# Conn_pcb5.net
KiCad netlist of a schematic drawn in EAGLE
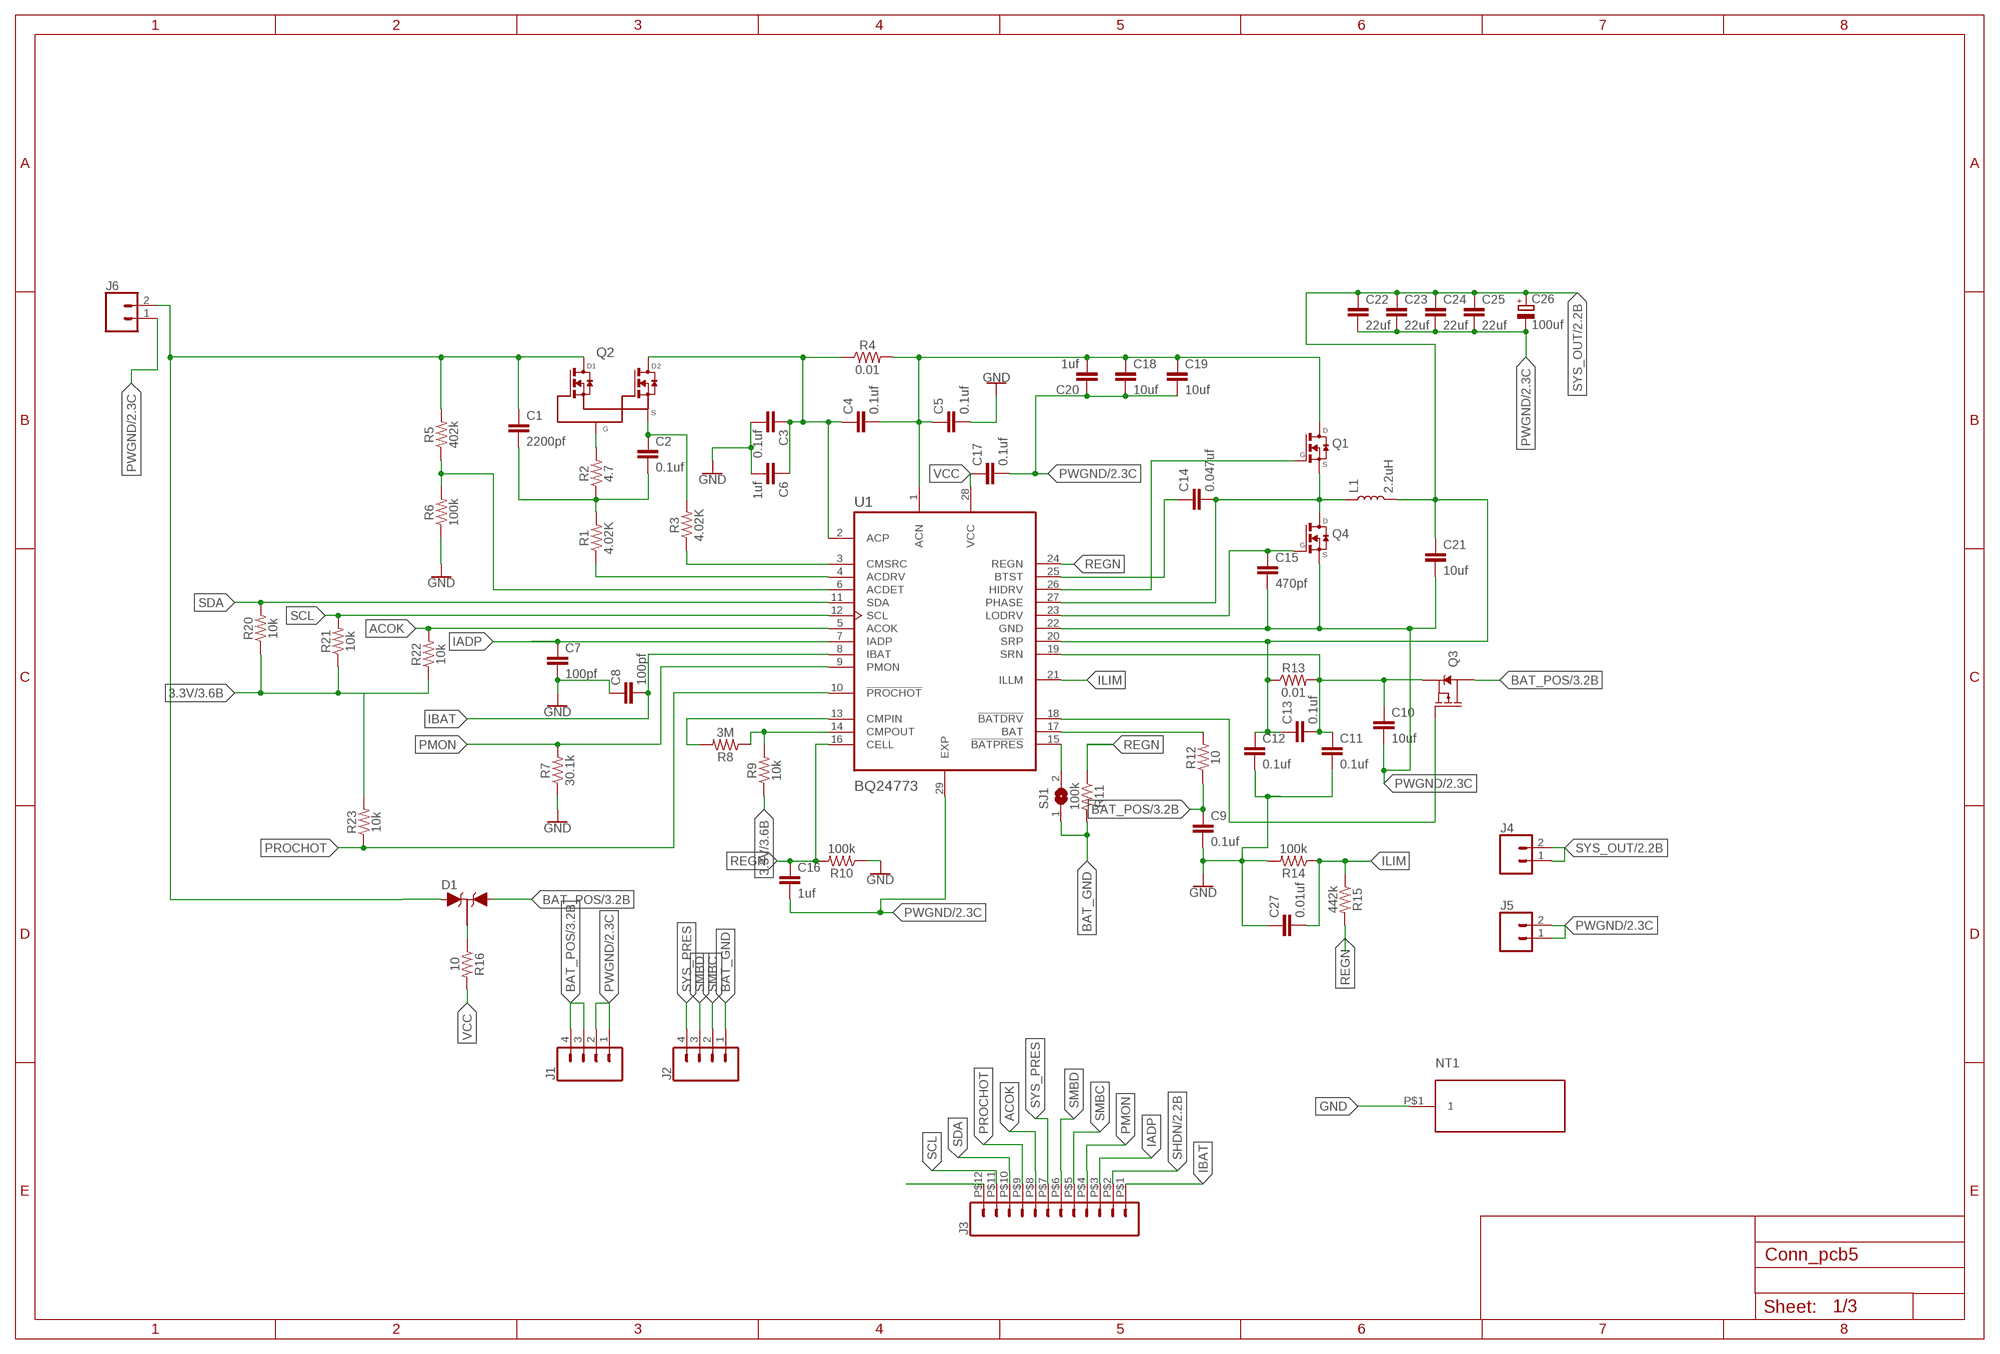
[diagram p0: schematic, sheet 1]
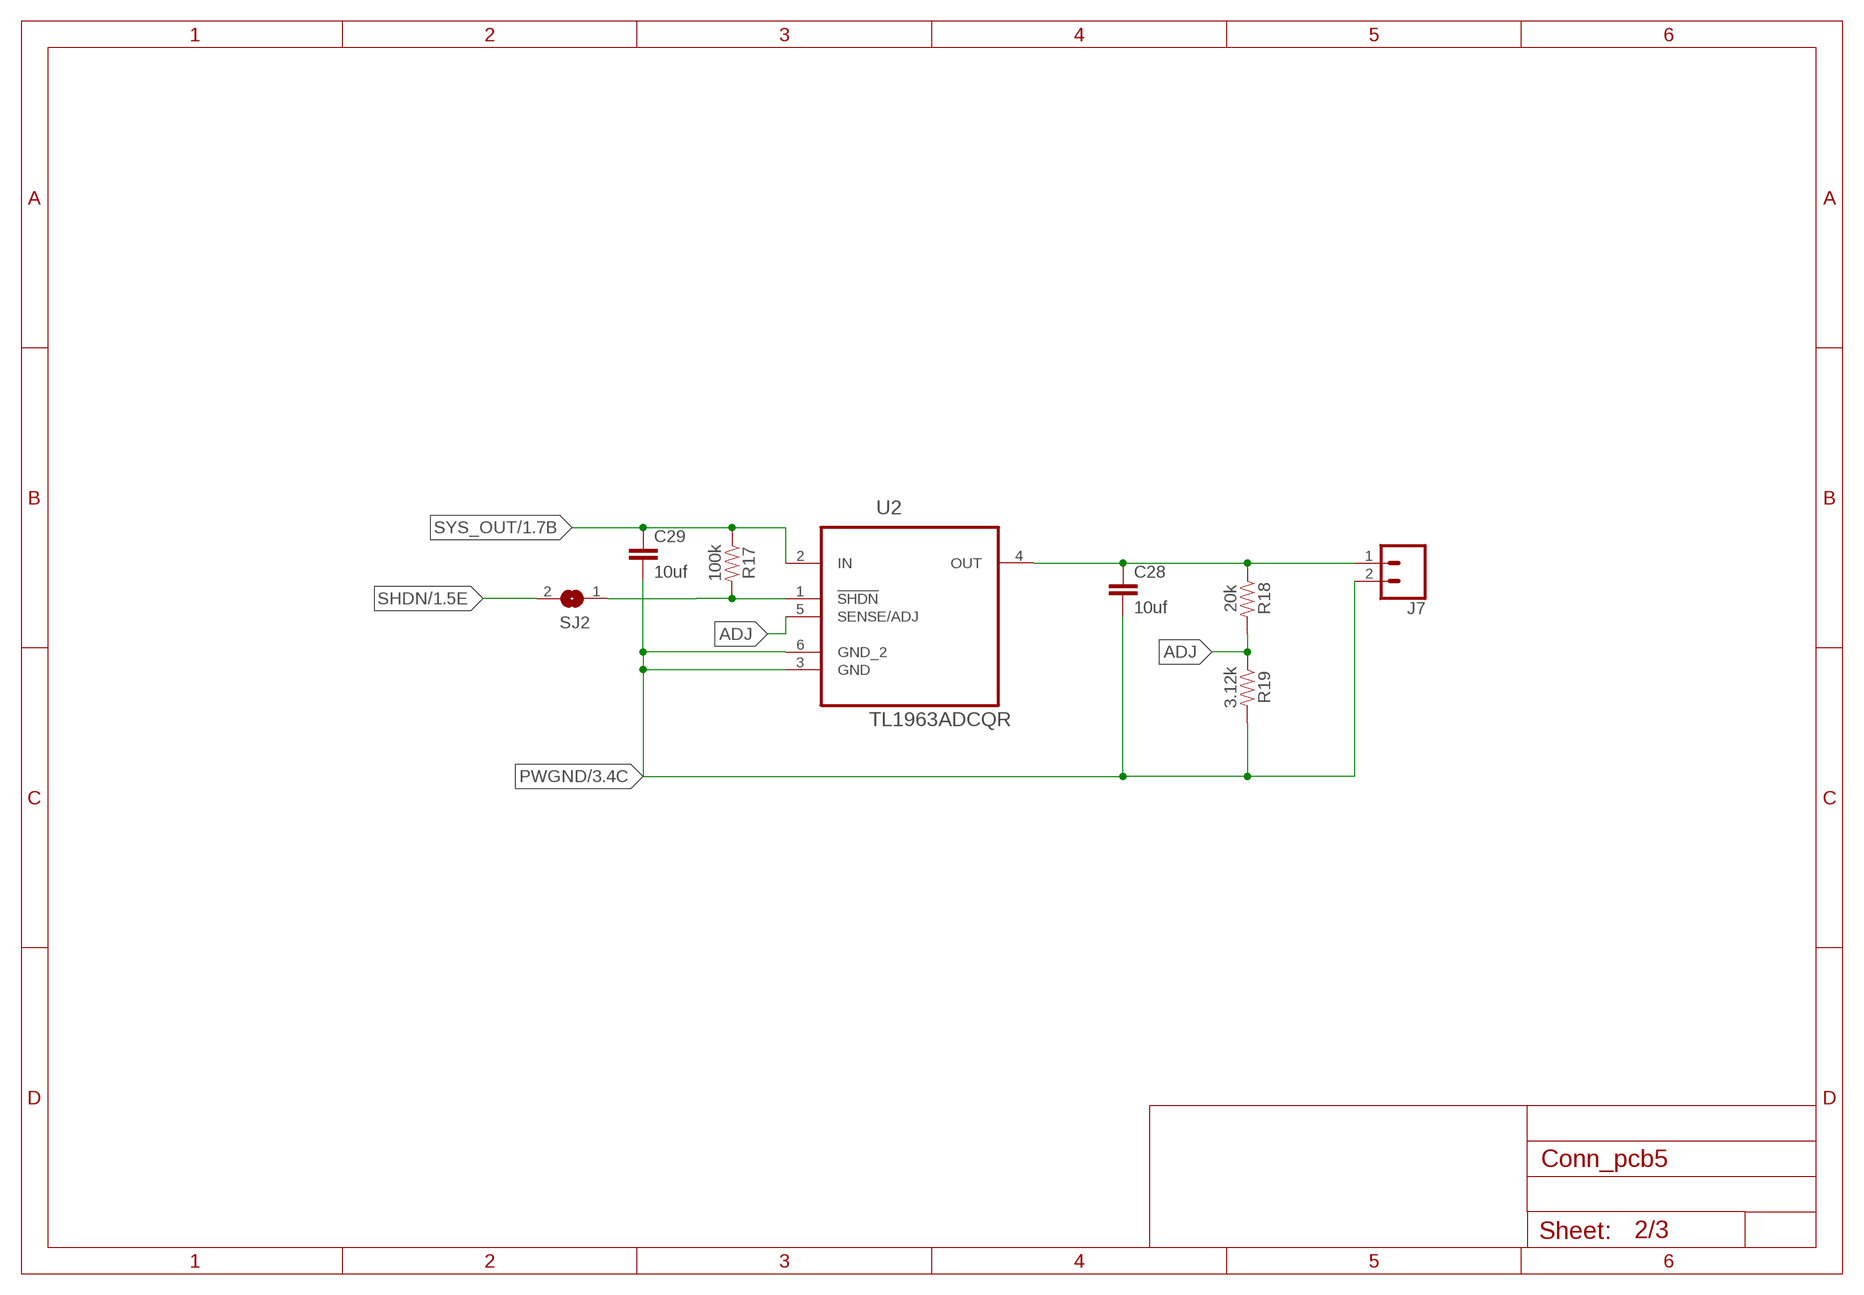
[diagram p1: schematic, sheet 2]
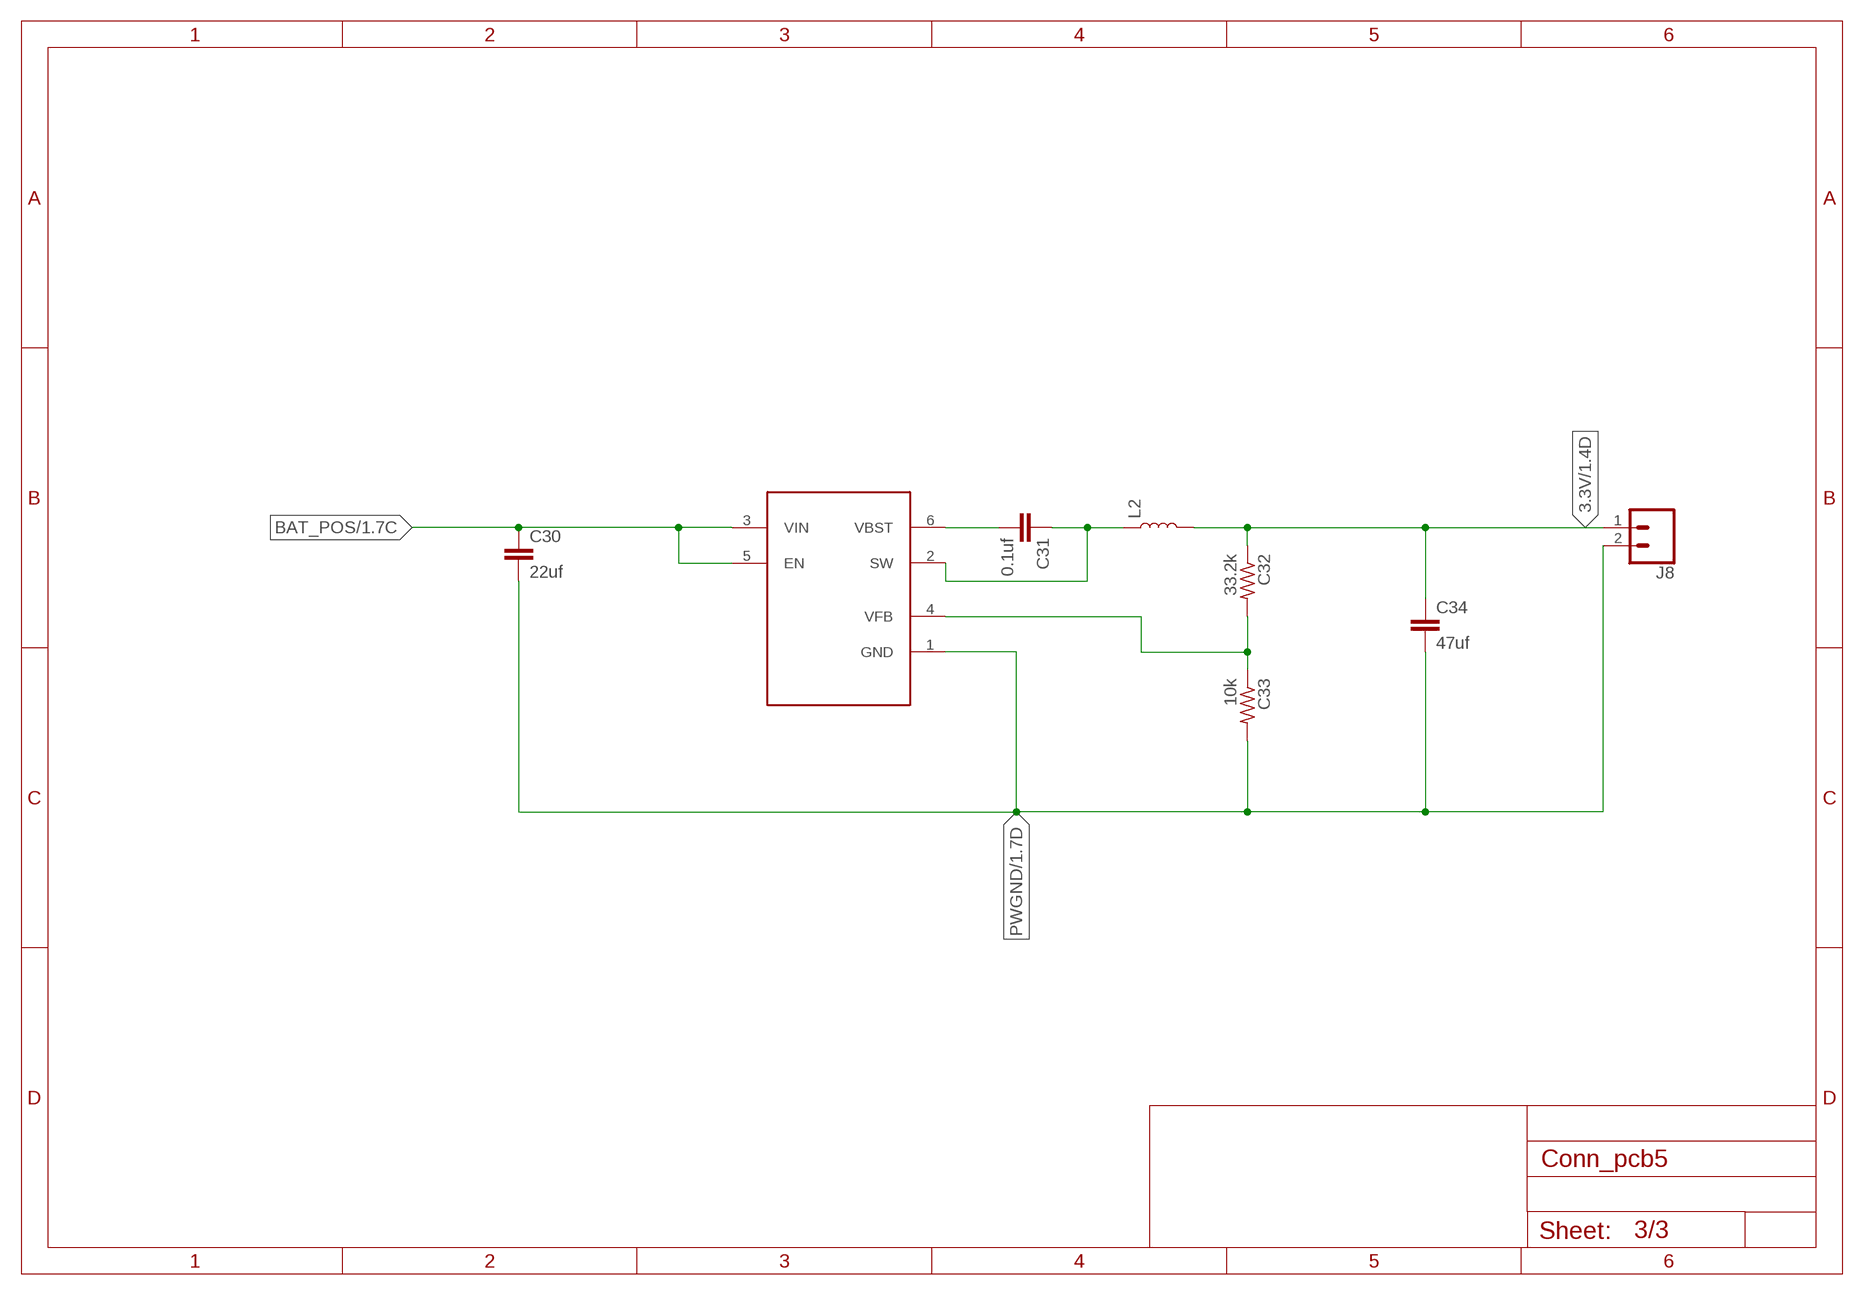
[diagram p2: schematic, sheet 3]

(export (version "E")
  (design (tool "Eeschema 10.0.6"))
  (components
    (comp (ref "C28")
      (value "10uf")
      (footprint "eagle-import:C0805K")
      (libsource (lib "eagle-import") (part "C-EUC0805K"))
    )
    (comp (ref "C29")
      (value "10uf")
      (footprint "eagle-import:C0805K")
      (libsource (lib "eagle-import") (part "C-EUC0805K"))
    )
    (comp (ref "J7")
      (value "CONN_02")
      (footprint "eagle-import:1X02")
      (libsource (lib "eagle-import") (part "CONN_02"))
    )
    (comp (ref "R17")
      (value "100k")
      (footprint "eagle-import:0402")
      (libsource (lib "eagle-import") (part "RES4K04020402"))
    )
    (comp (ref "R18")
      (value "20k")
      (footprint "eagle-import:0402")
      (libsource (lib "eagle-import") (part "RES4K04020402"))
    )
    (comp (ref "R19")
      (value "3.12k")
      (footprint "eagle-import:0402")
      (libsource (lib "eagle-import") (part "RES4K04020402"))
    )
    (comp (ref "SJ2") (value "SJ") (footprint "eagle-import:SJ") (libsource (lib "eagle-import") (part "SJ")))
    (comp (ref "U2")
      (value "TL1963ADCQR")
      (footprint "eagle-import:SOT127P706X180-6")
      (libsource (lib "eagle-import") (part "TL1963ADCQR"))
    )
    (comp (ref "C30")
      (value "22uf")
      (footprint "eagle-import:C1206")
      (libsource (lib "eagle-import") (part "C-EUC1206"))
    )
    (comp (ref "C31")
      (value "0.1uf")
      (footprint "eagle-import:CAPC1005X50")
      (libsource (lib "eagle-import") (part "CAP0402"))
    )
    (comp (ref "C32")
      (value "33.2k")
      (footprint "eagle-import:R0805")
      (libsource (lib "eagle-import") (part "R-US_R0805"))
    )
    (comp (ref "C33")
      (value "10k")
      (footprint "eagle-import:R0603")
      (libsource (lib "eagle-import") (part "R-US_R0603"))
    )
    (comp (ref "C34")
      (value "47uf")
      (footprint "eagle-import:C1206K")
      (libsource (lib "eagle-import") (part "C-EUC1206K"))
    )
    (comp (ref "J8")
      (value "CONN_02")
      (footprint "eagle-import:1X02")
      (libsource (lib "eagle-import") (part "CONN_02"))
    )
    (comp (ref "L2")
      (value "ASPI-4030S-3R3M-T")
      (footprint "eagle-import:INDDFN400X400X300-2")
      (libsource (lib "eagle-import") (part "ASPI-4030S-3R3M-T"))
    )
    (comp (ref "U3")
      (value "TPS561208DDCR")
      (footprint "eagle-import:SOT95P280X110-6")
      (libsource (lib "eagle-import") (part "TPS561208DDCR"))
    )
    (comp (ref "C1")
      (value "2200pf")
      (footprint "eagle-import:CAPC1005X50")
      (libsource (lib "eagle-import") (part "CAP0402"))
    )
    (comp (ref "C2")
      (value "0.1uf")
      (footprint "eagle-import:CAPC1005X50")
      (libsource (lib "eagle-import") (part "CAP0402"))
    )
    (comp (ref "C3")
      (value "0.1uf")
      (footprint "eagle-import:CAPC1005X50")
      (libsource (lib "eagle-import") (part "CAP0402"))
    )
    (comp (ref "C4")
      (value "0.1uf")
      (footprint "eagle-import:CAPC1005X50")
      (libsource (lib "eagle-import") (part "CAP0402"))
    )
    (comp (ref "C5")
      (value "0.1uf")
      (footprint "eagle-import:CAPC1005X50")
      (libsource (lib "eagle-import") (part "CAP0402"))
    )
    (comp (ref "C6")
      (value "1uf")
      (footprint "eagle-import:CAPC1005X50")
      (libsource (lib "eagle-import") (part "CAP0402"))
    )
    (comp (ref "C7")
      (value "100pf")
      (footprint "eagle-import:CAPC1005X50")
      (libsource (lib "eagle-import") (part "CAP0402"))
    )
    (comp (ref "C8")
      (value "100pf")
      (footprint "eagle-import:CAPC1005X50")
      (libsource (lib "eagle-import") (part "CAP0402"))
    )
    (comp (ref "C9")
      (value "0.1uf")
      (footprint "eagle-import:CAPC1005X50")
      (libsource (lib "eagle-import") (part "CAP0402"))
    )
    (comp (ref "C10")
      (value "10uf")
      (footprint "eagle-import:C0805K")
      (libsource (lib "eagle-import") (part "C-EUC0805K"))
    )
    (comp (ref "C11")
      (value "0.1uf")
      (footprint "eagle-import:CAPC1005X50")
      (libsource (lib "eagle-import") (part "CAP0402"))
    )
    (comp (ref "C12")
      (value "0.1uf")
      (footprint "eagle-import:CAPC1005X50")
      (libsource (lib "eagle-import") (part "CAP0402"))
    )
    (comp (ref "C13")
      (value "0.1uf")
      (footprint "eagle-import:CAPC1005X50")
      (libsource (lib "eagle-import") (part "CAP0402"))
    )
    (comp (ref "C14")
      (value "0.047uf")
      (footprint "eagle-import:CAPC1005X50")
      (libsource (lib "eagle-import") (part "CAP0402"))
    )
    (comp (ref "C15")
      (value "470pf")
      (footprint "eagle-import:CAPC1005X50")
      (libsource (lib "eagle-import") (part "CAP0402"))
    )
    (comp (ref "C16")
      (value "1uf")
      (footprint "eagle-import:CAPC1005X50")
      (libsource (lib "eagle-import") (part "CAP0402"))
    )
    (comp (ref "C17")
      (value "0.1uf")
      (footprint "eagle-import:CAPC1005X50")
      (libsource (lib "eagle-import") (part "CAP0402"))
    )
    (comp (ref "C18")
      (value "10uf")
      (footprint "eagle-import:C0805K")
      (libsource (lib "eagle-import") (part "C-EUC0805K"))
    )
    (comp (ref "C19")
      (value "10uf")
      (footprint "eagle-import:C0805K")
      (libsource (lib "eagle-import") (part "C-EUC0805K"))
    )
    (comp (ref "C20")
      (value "1uf")
      (footprint "eagle-import:CAPC1005X50")
      (libsource (lib "eagle-import") (part "CAP0402"))
    )
    (comp (ref "C21")
      (value "10uf")
      (footprint "eagle-import:C0805K")
      (libsource (lib "eagle-import") (part "C-EUC0805K"))
    )
    (comp (ref "C22")
      (value "22uf")
      (footprint "eagle-import:C1206")
      (libsource (lib "eagle-import") (part "C-EUC1206"))
    )
    (comp (ref "C23")
      (value "22uf")
      (footprint "eagle-import:C1206")
      (libsource (lib "eagle-import") (part "C-EUC1206"))
    )
    (comp (ref "C24")
      (value "22uf")
      (footprint "eagle-import:C1206")
      (libsource (lib "eagle-import") (part "C-EUC1206"))
    )
    (comp (ref "C25")
      (value "22uf")
      (footprint "eagle-import:C1206")
      (libsource (lib "eagle-import") (part "C-EUC1206"))
    )
    (comp (ref "C26")
      (value "100uf")
      (footprint "eagle-import:CAPAE1030X800")
      (libsource (lib "eagle-import") (part "16SVP100M"))
    )
    (comp (ref "C27")
      (value "0.01uf")
      (footprint "eagle-import:CAPC1005X50")
      (libsource (lib "eagle-import") (part "CAP0402"))
    )
    (comp (ref "D1")
      (value "BAT54C-7-F")
      (footprint "eagle-import:SOT95P235X110-3")
      (libsource (lib "eagle-import") (part "BAT54C-7-F"))
    )
    (comp (ref "J1")
      (value "CONN_041.3")
      (footprint "eagle-import:1X04_NO_SILK_1.3")
      (libsource (lib "eagle-import") (part "CONN_041.3"))
    )
    (comp (ref "J2")
      (value "CONN_041.3")
      (footprint "eagle-import:1X04_NO_SILK_1.3")
      (libsource (lib "eagle-import") (part "CONN_041.3"))
    )
    (comp (ref "J3")
      (value "62674-121121ALF")
      (footprint "eagle-import:62674-121121ALF")
      (libsource (lib "eagle-import") (part "62674-121121ALF"))
    )
    (comp (ref "J4")
      (value "CONN_021.4HOLE")
      (footprint "eagle-import:1X02_1.4HOLE")
      (libsource (lib "eagle-import") (part "CONN_021.4HOLE"))
    )
    (comp (ref "J5")
      (value "CONN_021.4HOLE")
      (footprint "eagle-import:1X02_1.4HOLE")
      (libsource (lib "eagle-import") (part "CONN_021.4HOLE"))
    )
    (comp (ref "J6")
      (value "CONN_021.4HOLE")
      (footprint "eagle-import:1X02_1.4HOLE")
      (libsource (lib "eagle-import") (part "CONN_021.4HOLE"))
    )
    (comp (ref "L1")
      (value "2.2uH")
      (footprint "eagle-import:RESM6365X610")
      (libsource (lib "eagle-import") (part "XEL6060-222MEB"))
    )
    (comp (ref "NT1")
      (value "NET_TIE")
      (footprint "eagle-import:NET_TIE")
      (libsource (lib "eagle-import") (part "NET_TIE"))
    )
    (comp (ref "Q1")
      (value "CSD17308Q3")
      (footprint "eagle-import:SON65P330X330X110-8")
      (fields (field (name "SPICEPREFIX") "Q"))
      (libsource (lib "eagle-import") (part "CSD17308Q3"))
    )
    (comp (ref "Q2")
      (value "CSD87312Q3EVSON")
      (footprint "eagle-import:QFN65P330X330X100-12")
      (libsource (lib "eagle-import") (part "CSD87312Q3EVSON"))
    )
    (comp (ref "Q3")
      (value "CSD25402Q3A")
      (footprint "eagle-import:CSD25402Q3A")
      (libsource (lib "eagle-import") (part "CSD25402Q3A"))
    )
    (comp (ref "Q4")
      (value "CSD17308Q3")
      (footprint "eagle-import:SON65P330X330X110-8")
      (fields (field (name "SPICEPREFIX") "Q"))
      (libsource (lib "eagle-import") (part "CSD17308Q3"))
    )
    (comp (ref "R1")
      (value "4.02K")
      (footprint "eagle-import:0402")
      (libsource (lib "eagle-import") (part "RES4K04020402"))
    )
    (comp (ref "R2")
      (value "4.7")
      (footprint "eagle-import:0402")
      (libsource (lib "eagle-import") (part "RES4K04020402"))
    )
    (comp (ref "R3")
      (value "4.02K")
      (footprint "eagle-import:0402")
      (libsource (lib "eagle-import") (part "RES4K04020402"))
    )
    (comp (ref "R4")
      (value "0.01")
      (footprint "eagle-import:1206")
      (libsource (lib "eagle-import") (part "SENSE-RES"))
    )
    (comp (ref "R5")
      (value "402k")
      (footprint "eagle-import:0402")
      (libsource (lib "eagle-import") (part "RES4K04020402"))
    )
    (comp (ref "R6")
      (value "100k")
      (footprint "eagle-import:0402")
      (libsource (lib "eagle-import") (part "RES4K04020402"))
    )
    (comp (ref "R7")
      (value "30.1k")
      (footprint "eagle-import:0402")
      (libsource (lib "eagle-import") (part "RES4K04020402"))
    )
    (comp (ref "R8")
      (value "3M")
      (footprint "eagle-import:0402")
      (libsource (lib "eagle-import") (part "RES4K04020402"))
    )
    (comp (ref "R9")
      (value "10k")
      (footprint "eagle-import:0402")
      (libsource (lib "eagle-import") (part "RES4K04020402"))
    )
    (comp (ref "R10")
      (value "100k")
      (footprint "eagle-import:0402")
      (libsource (lib "eagle-import") (part "RES4K04020402"))
    )
    (comp (ref "R11")
      (value "100k")
      (footprint "eagle-import:0402")
      (libsource (lib "eagle-import") (part "RES4K04020402"))
    )
    (comp (ref "R12")
      (value "10")
      (footprint "eagle-import:0402")
      (libsource (lib "eagle-import") (part "RES4K04020402"))
    )
    (comp (ref "R13")
      (value "0.01")
      (footprint "eagle-import:1206")
      (libsource (lib "eagle-import") (part "SENSE-RES"))
    )
    (comp (ref "R14")
      (value "100k")
      (footprint "eagle-import:0402")
      (libsource (lib "eagle-import") (part "RES4K04020402"))
    )
    (comp (ref "R15")
      (value "442k")
      (footprint "eagle-import:0402")
      (libsource (lib "eagle-import") (part "RES4K04020402"))
    )
    (comp (ref "R16")
      (value "10")
      (footprint "eagle-import:0402")
      (libsource (lib "eagle-import") (part "RES4K04020402"))
    )
    (comp (ref "R20")
      (value "10k")
      (footprint "eagle-import:0402")
      (libsource (lib "eagle-import") (part "RES4K04020402"))
    )
    (comp (ref "R21")
      (value "10k")
      (footprint "eagle-import:0402")
      (libsource (lib "eagle-import") (part "RES4K04020402"))
    )
    (comp (ref "R22")
      (value "10k")
      (footprint "eagle-import:0402")
      (libsource (lib "eagle-import") (part "RES4K04020402"))
    )
    (comp (ref "R23")
      (value "10k")
      (footprint "eagle-import:0402")
      (libsource (lib "eagle-import") (part "RES4K04020402"))
    )
    (comp (ref "SJ1") (value "SJ") (footprint "eagle-import:SJ") (libsource (lib "eagle-import") (part "SJ")))
    (comp (ref "U1")
      (value "BQ24773")
      (footprint "eagle-import:QFN40P400X400X80-29T240")
      (libsource (lib "eagle-import") (part "BQ24773"))
    )
  )
  (nets
    (net (code "1") (name "3.3V") (class "Default")
      (node (ref "C32") (pin "1") (pinfunction "1_1") (pintype "passive"))
      (node (ref "C34") (pin "1") (pinfunction "1_1") (pintype "passive"))
      (node (ref "J8") (pin "1") (pinfunction "1_1") (pintype "passive"))
      (node (ref "L2") (pin "2") (pinfunction "2_2") (pintype "passive"))
      (node (ref "R20") (pin "1") (pinfunction "1_1") (pintype "passive"))
      (node (ref "R21") (pin "1") (pinfunction "1_1") (pintype "passive"))
      (node (ref "R22") (pin "1") (pinfunction "1_1") (pintype "passive"))
      (node (ref "R23") (pin "2") (pinfunction "2_2") (pintype "passive"))
      (node (ref "R9") (pin "1") (pinfunction "1_1") (pintype "passive"))
    )
    (net (code "2") (name "ACOK") (class "Default")
      (node (ref "J3") (pin "P$8") (pinfunction "8_P$8") (pintype "passive"))
      (node (ref "R22") (pin "2") (pinfunction "2_2") (pintype "passive"))
      (node (ref "U1") (pin "5") (pinfunction "ACOK_5") (pintype "output"))
    )
    (net (code "3") (name "ADJ") (class "Default")
      (node (ref "R18") (pin "2") (pinfunction "2_2") (pintype "passive"))
      (node (ref "R19") (pin "1") (pinfunction "1_1") (pintype "passive"))
      (node (ref "U2") (pin "5") (pinfunction "SENSE/ADJ_5") (pintype "input"))
    )
    (net (code "4") (name "BAT_GND") (class "Default")
      (node (ref "J2") (pin "1") (pinfunction "1_1") (pintype "passive"))
      (node (ref "R11") (pin "2") (pinfunction "2_2") (pintype "passive"))
      (node (ref "SJ1") (pin "1") (pinfunction "1_1") (pintype "passive"))
    )
    (net (code "5") (name "BAT_POS") (class "Default")
      (node (ref "C30") (pin "1") (pinfunction "1_1") (pintype "passive"))
      (node (ref "C9") (pin "1") (pinfunction "1_1") (pintype "passive"))
      (node (ref "D1") (pin "2") (pinfunction "A2_2") (pintype "passive"))
      (node (ref "J1") (pin "3") (pinfunction "3_3") (pintype "passive"))
      (node (ref "J1") (pin "4") (pinfunction "4_4") (pintype "passive"))
      (node (ref "Q3") (pin "1") (pinfunction "D_1") (pintype "bidirectional"))
      (node (ref "Q3") (pin "2") (pinfunction "D_2") (pintype "bidirectional"))
      (node (ref "Q3") (pin "3") (pinfunction "D_3") (pintype "bidirectional"))
      (node (ref "R12") (pin "1") (pinfunction "1_1") (pintype "passive"))
      (node (ref "U3") (pin "3") (pinfunction "VIN_3") (pintype "bidirectional"))
      (node (ref "U3") (pin "5") (pinfunction "EN_5") (pintype "bidirectional"))
    )
    (net (code "6") (name "GND") (class "Default")
      (node (ref "C11") (pin "2") (pinfunction "2_2") (pintype "passive"))
      (node (ref "C12") (pin "2") (pinfunction "2_2") (pintype "passive"))
      (node (ref "C27") (pin "1") (pinfunction "1_1") (pintype "passive"))
      (node (ref "C3") (pin "2") (pinfunction "2_2") (pintype "passive"))
      (node (ref "C5") (pin "2") (pinfunction "2_2") (pintype "passive"))
      (node (ref "C6") (pin "2") (pinfunction "2_2") (pintype "passive"))
      (node (ref "C7") (pin "2") (pinfunction "2_2") (pintype "passive"))
      (node (ref "C8") (pin "1") (pinfunction "1_1") (pintype "passive"))
      (node (ref "C9") (pin "2") (pinfunction "2_2") (pintype "passive"))
      (node (ref "NT1") (pin "P$1") (pinfunction "1_P$1") (pintype "bidirectional"))
      (node (ref "R10") (pin "1") (pinfunction "1_1") (pintype "passive"))
      (node (ref "R14") (pin "2") (pinfunction "2_2") (pintype "passive"))
      (node (ref "R6") (pin "1") (pinfunction "1_1") (pintype "passive"))
      (node (ref "R7") (pin "1") (pinfunction "1_1") (pintype "passive"))
    )
    (net (code "7") (name "IADP") (class "Default")
      (node (ref "C7") (pin "1") (pinfunction "1_1") (pintype "passive"))
      (node (ref "J3") (pin "P$3") (pinfunction "3_P$3") (pintype "passive"))
      (node (ref "U1") (pin "7") (pinfunction "IADP_7") (pintype "output"))
    )
    (net (code "8") (name "IBAT") (class "Default")
      (node (ref "C8") (pin "2") (pinfunction "2_2") (pintype "passive"))
      (node (ref "J3") (pin "P$1") (pinfunction "1_P$1") (pintype "passive"))
      (node (ref "U1") (pin "8") (pinfunction "IBAT_8") (pintype "output"))
    )
    (net (code "9") (name "ILIM") (class "Default")
      (node (ref "C27") (pin "2") (pinfunction "2_2") (pintype "passive"))
      (node (ref "R14") (pin "1") (pinfunction "1_1") (pintype "passive"))
      (node (ref "R15") (pin "1") (pinfunction "1_1") (pintype "passive"))
      (node (ref "U1") (pin "21") (pinfunction "ILLM_21") (pintype "input"))
    )
    (net (code "10") (name "Net-(C1-Pad2)") (class "Default")
      (node (ref "C1") (pin "2") (pinfunction "2_2") (pintype "passive"))
      (node (ref "C2") (pin "2") (pinfunction "2_2") (pintype "passive"))
      (node (ref "R1") (pin "2") (pinfunction "2_2") (pintype "passive"))
      (node (ref "R2") (pin "1") (pinfunction "1_1") (pintype "passive"))
    )
    (net (code "11") (name "Net-(C2-Pad1)") (class "Default")
      (node (ref "C2") (pin "1") (pinfunction "1_1") (pintype "passive"))
      (node (ref "Q2") (pin "9") (pinfunction "S_9") (pintype "passive"))
      (node (ref "Q2") (pin "9.1") (pinfunction "S_9.1") (pintype "passive"))
      (node (ref "Q2") (pin "9.2") (pinfunction "S_9.2") (pintype "passive"))
      (node (ref "Q2") (pin "9.3") (pinfunction "S_9.3") (pintype "passive"))
      (node (ref "Q2") (pin "9.4") (pinfunction "S_9.4") (pintype "passive"))
      (node (ref "R3") (pin "2") (pinfunction "2_2") (pintype "passive"))
    )
    (net (code "12") (name "Net-(D1-A1)") (class "Default")
      (node (ref "C1") (pin "1") (pinfunction "1_1") (pintype "passive"))
      (node (ref "D1") (pin "1") (pinfunction "A1_1") (pintype "passive"))
      (node (ref "J6") (pin "2") (pinfunction "2_2") (pintype "passive"))
      (node (ref "Q2") (pin "1") (pinfunction "D1_1") (pintype "passive"))
      (node (ref "Q2") (pin "3") (pinfunction "D1_3") (pintype "passive"))
      (node (ref "Q2") (pin "4") (pinfunction "D1_4") (pintype "passive"))
      (node (ref "R5") (pin "2") (pinfunction "2_2") (pintype "passive"))
    )
    (net (code "13") (name "Net-(D1-K)") (class "Default")
      (node (ref "D1") (pin "3") (pinfunction "K_3") (pintype "passive"))
      (node (ref "R16") (pin "1") (pinfunction "1_1") (pintype "passive"))
    )
    (net (code "14") (name "Net-(Q1-G)") (class "Default")
      (node (ref "Q1") (pin "4") (pinfunction "G_4") (pintype "passive"))
      (node (ref "U1") (pin "26") (pinfunction "HIDRV_26") (pintype "output"))
    )
    (net (code "15") (name "Net-(Q2-G)") (class "Default")
      (node (ref "Q2") (pin "5") (pinfunction "G_5") (pintype "passive"))
      (node (ref "R2") (pin "2") (pinfunction "2_2") (pintype "passive"))
    )
    (net (code "16") (name "Net-(Q3-G)") (class "Default")
      (node (ref "Q3") (pin "4") (pinfunction "G_4") (pintype "bidirectional"))
      (node (ref "U1") (pin "18") (pinfunction "~{BATDRV}_18") (pintype "output"))
    )
    (net (code "17") (name "Net-(Q4-G)") (class "Default")
      (node (ref "C15") (pin "1") (pinfunction "1_1") (pintype "passive"))
      (node (ref "Q4") (pin "4") (pinfunction "G_4") (pintype "passive"))
      (node (ref "U1") (pin "23") (pinfunction "LODRV_23") (pintype "output"))
    )
    (net (code "18") (name "Net-(U1-ACDET)") (class "Default")
      (node (ref "R5") (pin "1") (pinfunction "1_1") (pintype "passive"))
      (node (ref "R6") (pin "2") (pinfunction "2_2") (pintype "passive"))
      (node (ref "U1") (pin "6") (pinfunction "ACDET_6") (pintype "input"))
    )
    (net (code "19") (name "Net-(U1-ACDRV)") (class "Default")
      (node (ref "R1") (pin "1") (pinfunction "1_1") (pintype "passive"))
      (node (ref "U1") (pin "4") (pinfunction "ACDRV_4") (pintype "output"))
    )
    (net (code "20") (name "Net-(U1-ACN)") (class "Default")
      (node (ref "C18") (pin "1") (pinfunction "1_1") (pintype "passive"))
      (node (ref "C19") (pin "1") (pinfunction "1_1") (pintype "passive"))
      (node (ref "C20") (pin "2") (pinfunction "2_2") (pintype "passive"))
      (node (ref "C4") (pin "2") (pinfunction "2_2") (pintype "passive"))
      (node (ref "C5") (pin "1") (pinfunction "1_1") (pintype "passive"))
      (node (ref "Q1") (pin "5") (pinfunction "D_5") (pintype "passive"))
      (node (ref "Q1") (pin "6") (pinfunction "D_6") (pintype "passive"))
      (node (ref "Q1") (pin "7") (pinfunction "D_7") (pintype "passive"))
      (node (ref "Q1") (pin "8") (pinfunction "D_8") (pintype "passive"))
      (node (ref "R4") (pin "2") (pinfunction "2_2") (pintype "passive"))
      (node (ref "U1") (pin "1") (pinfunction "ACN_1") (pintype "input"))
    )
    (net (code "21") (name "Net-(U1-ACP)") (class "Default")
      (node (ref "C3") (pin "1") (pinfunction "1_1") (pintype "passive"))
      (node (ref "C4") (pin "1") (pinfunction "1_1") (pintype "passive"))
      (node (ref "C6") (pin "1") (pinfunction "1_1") (pintype "passive"))
      (node (ref "Q2") (pin "6") (pinfunction "D2_6") (pintype "passive"))
      (node (ref "Q2") (pin "7") (pinfunction "D2_7") (pintype "passive"))
      (node (ref "Q2") (pin "8") (pinfunction "D2_8") (pintype "passive"))
      (node (ref "R4") (pin "1") (pinfunction "1_1") (pintype "passive"))
      (node (ref "U1") (pin "2") (pinfunction "ACP_2") (pintype "input"))
    )
    (net (code "22") (name "Net-(U1-BAT)") (class "Default")
      (node (ref "R12") (pin "2") (pinfunction "2_2") (pintype "passive"))
      (node (ref "U1") (pin "17") (pinfunction "BAT_17") (pintype "input"))
    )
    (net (code "23") (name "Net-(U1-BTST)") (class "Default")
      (node (ref "C14") (pin "1") (pinfunction "1_1") (pintype "passive"))
      (node (ref "U1") (pin "25") (pinfunction "BTST_25") (pintype "passive"))
    )
    (net (code "24") (name "Net-(U1-CMPIN)") (class "Default")
      (node (ref "R8") (pin "2") (pinfunction "2_2") (pintype "passive"))
      (node (ref "U1") (pin "13") (pinfunction "CMPIN_13") (pintype "input"))
    )
    (net (code "25") (name "Net-(U1-CMPOUT)") (class "Default")
      (node (ref "R8") (pin "1") (pinfunction "1_1") (pintype "passive"))
      (node (ref "R9") (pin "2") (pinfunction "2_2") (pintype "passive"))
      (node (ref "U1") (pin "14") (pinfunction "CMPOUT_14") (pintype "output"))
    )
    (net (code "26") (name "Net-(U1-CMSRC)") (class "Default")
      (node (ref "R3") (pin "1") (pinfunction "1_1") (pintype "passive"))
      (node (ref "U1") (pin "3") (pinfunction "CMSRC_3") (pintype "input"))
    )
    (net (code "27") (name "Net-(U1-PHASE)") (class "Default")
      (node (ref "C14") (pin "2") (pinfunction "2_2") (pintype "passive"))
      (node (ref "L1") (pin "1") (pinfunction "1_1") (pintype "passive"))
      (node (ref "Q1") (pin "1") (pinfunction "S_1") (pintype "passive"))
      (node (ref "Q1") (pin "2") (pinfunction "S_2") (pintype "passive"))
      (node (ref "Q1") (pin "3") (pinfunction "S_3") (pintype "passive"))
      (node (ref "Q4") (pin "5") (pinfunction "D_5") (pintype "passive"))
      (node (ref "Q4") (pin "6") (pinfunction "D_6") (pintype "passive"))
      (node (ref "Q4") (pin "7") (pinfunction "D_7") (pintype "passive"))
      (node (ref "Q4") (pin "8") (pinfunction "D_8") (pintype "passive"))
      (node (ref "U1") (pin "27") (pinfunction "PHASE_27") (pintype "output"))
    )
    (net (code "28") (name "Net-(U1-SRN)") (class "Default")
      (node (ref "C10") (pin "1") (pinfunction "1_1") (pintype "passive"))
      (node (ref "C11") (pin "1") (pinfunction "1_1") (pintype "passive"))
      (node (ref "C13") (pin "2") (pinfunction "2_2") (pintype "passive"))
      (node (ref "Q3") (pin "5") (pinfunction "S_5") (pintype "bidirectional"))
      (node (ref "Q3") (pin "6") (pinfunction "S_6") (pintype "bidirectional"))
      (node (ref "Q3") (pin "7") (pinfunction "S_7") (pintype "bidirectional"))
      (node (ref "Q3") (pin "8") (pinfunction "S_8") (pintype "bidirectional"))
      (node (ref "Q3") (pin "9") (pinfunction "S_9") (pintype "bidirectional"))
      (node (ref "R13") (pin "2") (pinfunction "2_2") (pintype "passive"))
      (node (ref "U1") (pin "19") (pinfunction "SRN_19") (pintype "input"))
    )
    (net (code "29") (name "Net-(U1-~{BATPRES})") (class "Default")
      (node (ref "SJ1") (pin "2") (pinfunction "2_2") (pintype "passive"))
      (node (ref "U1") (pin "15") (pinfunction "~{BATPRES}_15") (pintype "input"))
    )
    (net (code "30") (name "Net-(U2-OUT)") (class "Default")
      (node (ref "C28") (pin "1") (pinfunction "1_1") (pintype "passive"))
      (node (ref "J7") (pin "1") (pinfunction "1_1") (pintype "passive"))
      (node (ref "R18") (pin "1") (pinfunction "1_1") (pintype "passive"))
      (node (ref "U2") (pin "4") (pinfunction "OUT_4") (pintype "output"))
    )
    (net (code "31") (name "Net-(U2-~{SHDN})") (class "Default")
      (node (ref "R17") (pin "2") (pinfunction "2_2") (pintype "passive"))
      (node (ref "SJ2") (pin "1") (pinfunction "1_1") (pintype "passive"))
      (node (ref "U2") (pin "1") (pinfunction "~{SHDN}_1") (pintype "input"))
    )
    (net (code "32") (name "Net-(U3-SW)") (class "Default")
      (node (ref "C31") (pin "1") (pinfunction "1_1") (pintype "passive"))
      (node (ref "L2") (pin "1") (pinfunction "1_1") (pintype "passive"))
      (node (ref "U3") (pin "2") (pinfunction "SW_2") (pintype "bidirectional"))
    )
    (net (code "33") (name "Net-(U3-VBST)") (class "Default")
      (node (ref "C31") (pin "2") (pinfunction "2_2") (pintype "passive"))
      (node (ref "U3") (pin "6") (pinfunction "VBST_6") (pintype "bidirectional"))
    )
    (net (code "34") (name "Net-(U3-VFB)") (class "Default")
      (node (ref "C32") (pin "2") (pinfunction "2_2") (pintype "passive"))
      (node (ref "C33") (pin "1") (pinfunction "1_1") (pintype "passive"))
      (node (ref "U3") (pin "4") (pinfunction "VFB_4") (pintype "bidirectional"))
    )
    (net (code "35") (name "PMON") (class "Default")
      (node (ref "J3") (pin "P$4") (pinfunction "4_P$4") (pintype "passive"))
      (node (ref "R7") (pin "2") (pinfunction "2_2") (pintype "passive"))
      (node (ref "U1") (pin "9") (pinfunction "PMON_9") (pintype "output"))
    )
    (net (code "36") (name "PROCHOT") (class "Default")
      (node (ref "J3") (pin "P$9") (pinfunction "9_P$9") (pintype "passive"))
      (node (ref "R23") (pin "1") (pinfunction "1_1") (pintype "passive"))
      (node (ref "U1") (pin "10") (pinfunction "~{PROCHOT}_10") (pintype "output"))
    )
    (net (code "37") (name "PWGND") (class "Default")
      (node (ref "C10") (pin "2") (pinfunction "2_2") (pintype "passive"))
      (node (ref "C15") (pin "2") (pinfunction "2_2") (pintype "passive"))
      (node (ref "C16") (pin "2") (pinfunction "2_2") (pintype "passive"))
      (node (ref "C17") (pin "2") (pinfunction "2_2") (pintype "passive"))
      (node (ref "C18") (pin "2") (pinfunction "2_2") (pintype "passive"))
      (node (ref "C19") (pin "2") (pinfunction "2_2") (pintype "passive"))
      (node (ref "C20") (pin "1") (pinfunction "1_1") (pintype "passive"))
      (node (ref "C21") (pin "2") (pinfunction "2_2") (pintype "passive"))
      (node (ref "C22") (pin "2") (pinfunction "2_2") (pintype "passive"))
      (node (ref "C23") (pin "2") (pinfunction "2_2") (pintype "passive"))
      (node (ref "C24") (pin "2") (pinfunction "2_2") (pintype "passive"))
      (node (ref "C25") (pin "2") (pinfunction "2_2") (pintype "passive"))
      (node (ref "C26") (pin "2") (pinfunction "-_2") (pintype "passive"))
      (node (ref "C28") (pin "2") (pinfunction "2_2") (pintype "passive"))
      (node (ref "C29") (pin "2") (pinfunction "2_2") (pintype "passive"))
      (node (ref "C30") (pin "2") (pinfunction "2_2") (pintype "passive"))
      (node (ref "C33") (pin "2") (pinfunction "2_2") (pintype "passive"))
      (node (ref "C34") (pin "2") (pinfunction "2_2") (pintype "passive"))
      (node (ref "J1") (pin "1") (pinfunction "1_1") (pintype "passive"))
      (node (ref "J1") (pin "2") (pinfunction "2_2") (pintype "passive"))
      (node (ref "J5") (pin "1") (pinfunction "1_1") (pintype "passive"))
      (node (ref "J5") (pin "2") (pinfunction "2_2") (pintype "passive"))
      (node (ref "J6") (pin "1") (pinfunction "1_1") (pintype "passive"))
      (node (ref "J7") (pin "2") (pinfunction "2_2") (pintype "passive"))
      (node (ref "J8") (pin "2") (pinfunction "2_2") (pintype "passive"))
      (node (ref "Q4") (pin "1") (pinfunction "S_1") (pintype "passive"))
      (node (ref "Q4") (pin "2") (pinfunction "S_2") (pintype "passive"))
      (node (ref "Q4") (pin "3") (pinfunction "S_3") (pintype "passive"))
      (node (ref "R19") (pin "2") (pinfunction "2_2") (pintype "passive"))
      (node (ref "U1") (pin "22") (pinfunction "GND_22") (pintype "power_in"))
      (node (ref "U1") (pin "29") (pinfunction "EXP_29") (pintype "power_in"))
      (node (ref "U2") (pin "3") (pinfunction "GND_3") (pintype "passive"))
      (node (ref "U2") (pin "6") (pinfunction "GND_2_6") (pintype "input"))
      (node (ref "U3") (pin "1") (pinfunction "GND_1") (pintype "bidirectional"))
    )
    (net (code "38") (name "REGN") (class "Default")
      (node (ref "C16") (pin "1") (pinfunction "1_1") (pintype "passive"))
      (node (ref "R10") (pin "2") (pinfunction "2_2") (pintype "passive"))
      (node (ref "R11") (pin "1") (pinfunction "1_1") (pintype "passive"))
      (node (ref "R15") (pin "2") (pinfunction "2_2") (pintype "passive"))
      (node (ref "U1") (pin "16") (pinfunction "CELL_16") (pintype "input"))
      (node (ref "U1") (pin "24") (pinfunction "REGN_24") (pintype "output"))
    )
    (net (code "39") (name "SCL") (class "Default")
      (node (ref "J3") (pin "P$11") (pinfunction "11_P$11") (pintype "passive"))
      (node (ref "R21") (pin "2") (pinfunction "2_2") (pintype "passive"))
      (node (ref "U1") (pin "12") (pinfunction "SCL_12") (pintype "input"))
    )
    (net (code "40") (name "SDA") (class "Default")
      (node (ref "J3") (pin "P$10") (pinfunction "10_P$10") (pintype "passive"))
      (node (ref "R20") (pin "2") (pinfunction "2_2") (pintype "passive"))
      (node (ref "U1") (pin "11") (pinfunction "SDA_11") (pintype "bidirectional"))
    )
    (net (code "41") (name "SHDN") (class "Default")
      (node (ref "J3") (pin "P$2") (pinfunction "2_P$2") (pintype "passive"))
      (node (ref "SJ2") (pin "2") (pinfunction "2_2") (pintype "passive"))
    )
    (net (code "42") (name "SMBC") (class "Default")
      (node (ref "J2") (pin "2") (pinfunction "2_2") (pintype "passive"))
      (node (ref "J3") (pin "P$5") (pinfunction "5_P$5") (pintype "passive"))
    )
    (net (code "43") (name "SMBD") (class "Default")
      (node (ref "J2") (pin "3") (pinfunction "3_3") (pintype "passive"))
      (node (ref "J3") (pin "P$6") (pinfunction "6_P$6") (pintype "passive"))
    )
    (net (code "44") (name "SYS_OUT") (class "Default")
      (node (ref "C12") (pin "1") (pinfunction "1_1") (pintype "passive"))
      (node (ref "C13") (pin "1") (pinfunction "1_1") (pintype "passive"))
      (node (ref "C21") (pin "1") (pinfunction "1_1") (pintype "passive"))
      (node (ref "C22") (pin "1") (pinfunction "1_1") (pintype "passive"))
      (node (ref "C23") (pin "1") (pinfunction "1_1") (pintype "passive"))
      (node (ref "C24") (pin "1") (pinfunction "1_1") (pintype "passive"))
      (node (ref "C25") (pin "1") (pinfunction "1_1") (pintype "passive"))
      (node (ref "C26") (pin "1") (pinfunction "+_1") (pintype "passive"))
      (node (ref "C29") (pin "1") (pinfunction "1_1") (pintype "passive"))
      (node (ref "J4") (pin "1") (pinfunction "1_1") (pintype "passive"))
      (node (ref "J4") (pin "2") (pinfunction "2_2") (pintype "passive"))
      (node (ref "L1") (pin "2") (pinfunction "2_2") (pintype "passive"))
      (node (ref "R13") (pin "1") (pinfunction "1_1") (pintype "passive"))
      (node (ref "R17") (pin "1") (pinfunction "1_1") (pintype "passive"))
      (node (ref "U1") (pin "20") (pinfunction "SRP_20") (pintype "input"))
      (node (ref "U2") (pin "2") (pinfunction "IN_2") (pintype "input"))
    )
    (net (code "45") (name "SYS_PRES") (class "Default")
      (node (ref "J2") (pin "4") (pinfunction "4_4") (pintype "passive"))
      (node (ref "J3") (pin "P$7") (pinfunction "7_P$7") (pintype "passive"))
    )
    (net (code "46") (name "VCC") (class "Default")
      (node (ref "C17") (pin "1") (pinfunction "1_1") (pintype "passive"))
      (node (ref "R16") (pin "2") (pinfunction "2_2") (pintype "passive"))
      (node (ref "U1") (pin "28") (pinfunction "VCC_28") (pintype "power_in"))
    )
    (net (code "47") (name "unconnected-(J3-12-PadP$12)") (class "Default")
      (node (ref "J3") (pin "P$12") (pinfunction "12_P$12") (pintype "passive"))
    )
  )
)
